# Temp_controlled_fan_2.net
KiCad netlist of a schematic drawn in EAGLE
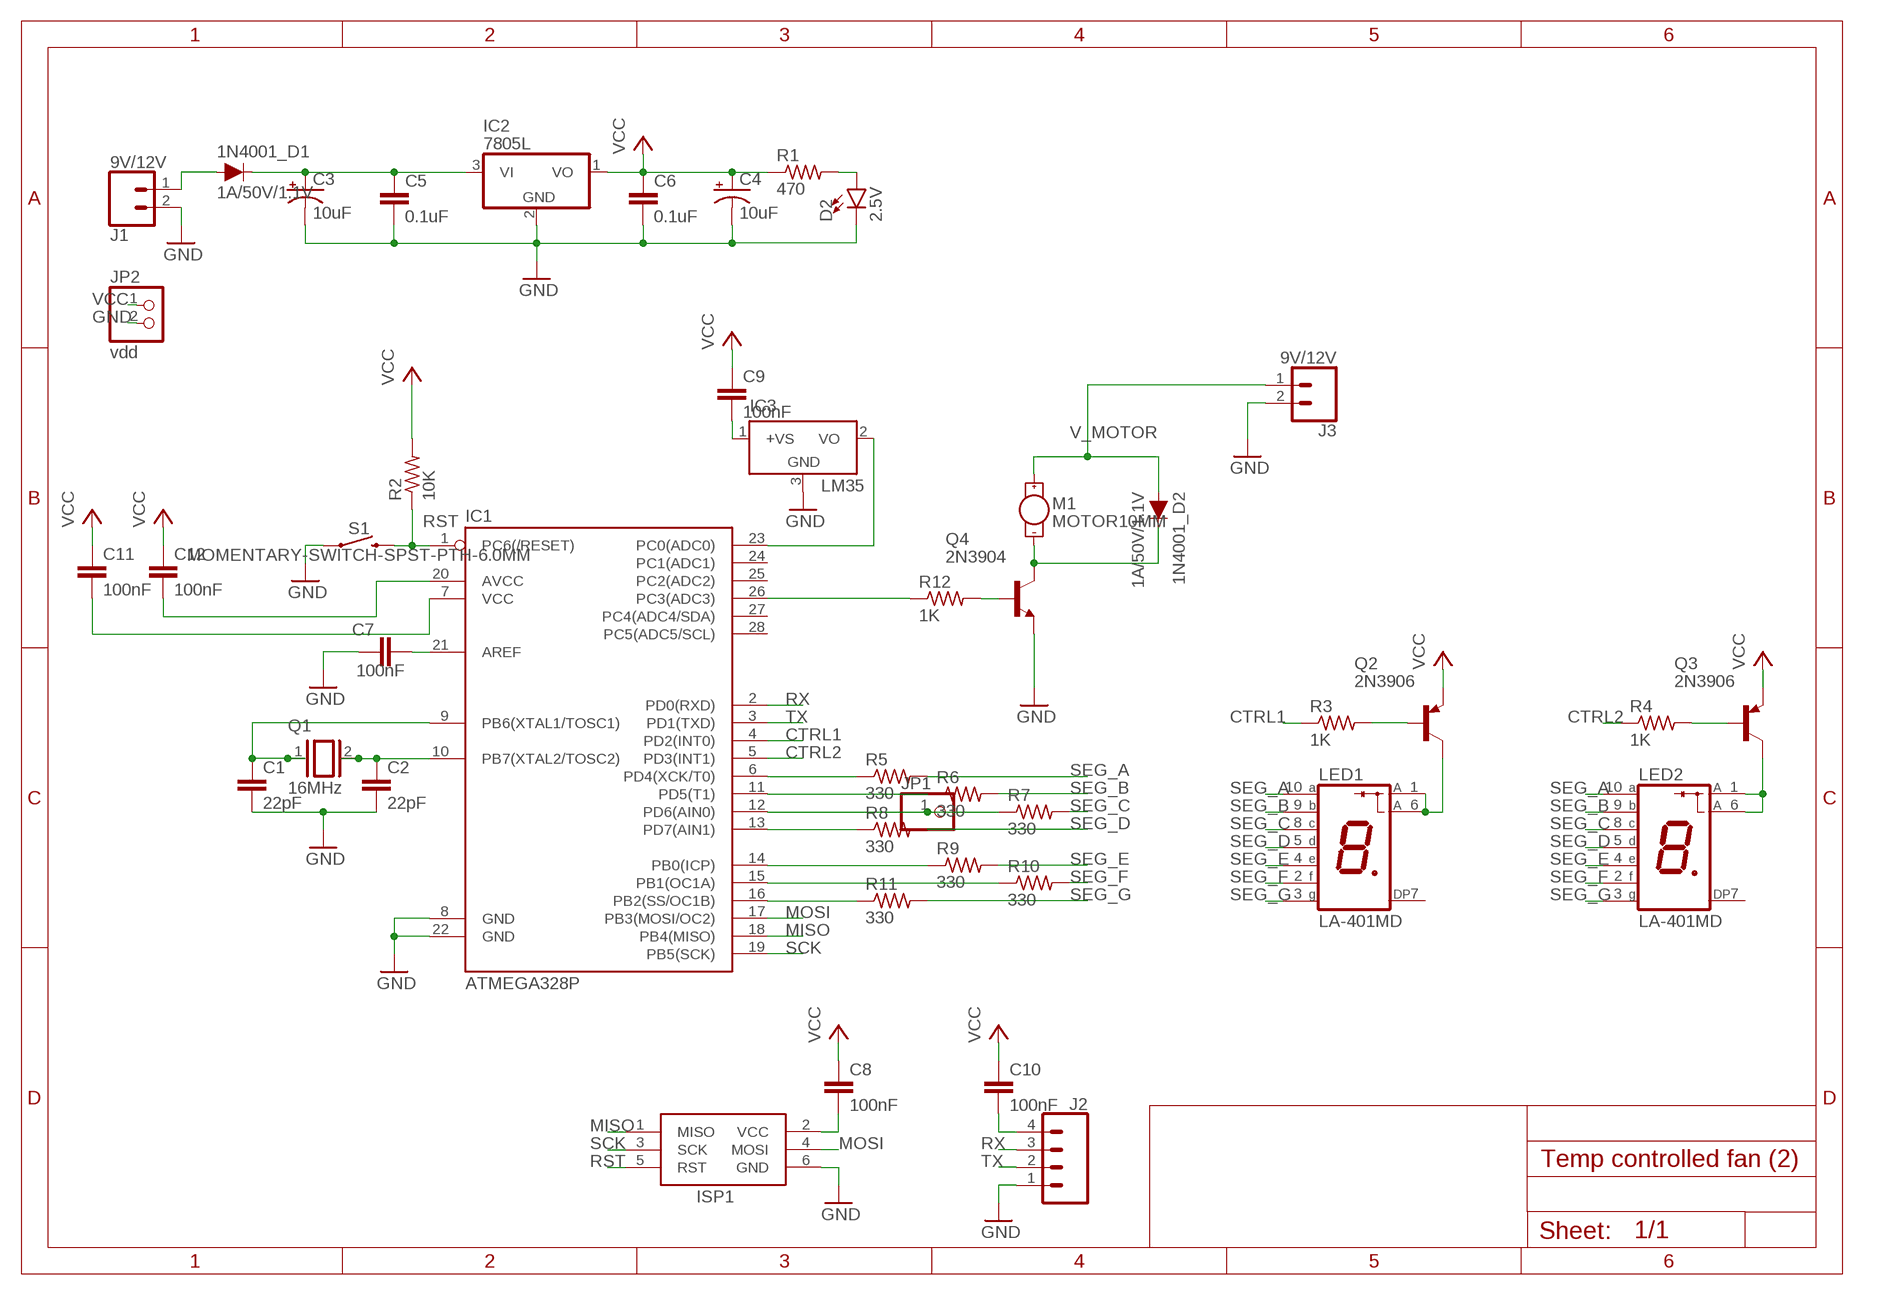
[diagram p0: schematic, sheet 1]

(export (version "E")
  (design (tool "Eeschema 10.0.6"))
  (components
    (comp (ref "1N4001_D1")
      (value "1A/50V/1.1V")
      (footprint "eagle-import:DIODE-1N4001")
      (libsource (lib "eagle-import") (part "DIODE-PTH"))
    )
    (comp (ref "1N4001_D2")
      (value "1A/50V/1.1V")
      (footprint "eagle-import:DIODE-1N4001")
      (libsource (lib "eagle-import") (part "DIODE-PTH"))
    )
    (comp (ref "C1")
      (value "22pF")
      (footprint "eagle-import:0603")
      (libsource (lib "eagle-import") (part "22PF-0603-50V-5%"))
    )
    (comp (ref "C2")
      (value "22pF")
      (footprint "eagle-import:0603")
      (libsource (lib "eagle-import") (part "22PF-0603-50V-5%"))
    )
    (comp (ref "C3")
      (value "10uF")
      (footprint "eagle-import:CPOL-RADIAL-2.5MM-5MM")
      (libsource (lib "eagle-import") (part "10UF-POLAR-RADIAL-2.5MM-25V-20%"))
    )
    (comp (ref "C4")
      (value "10uF")
      (footprint "eagle-import:CPOL-RADIAL-2.5MM-5MM")
      (libsource (lib "eagle-import") (part "10UF-POLAR-RADIAL-2.5MM-25V-20%"))
    )
    (comp (ref "C5")
      (value "0.1uF")
      (footprint "eagle-import:0603")
      (libsource (lib "eagle-import") (part "0.1UF-0603-25V-5%"))
    )
    (comp (ref "C6")
      (value "0.1uF")
      (footprint "eagle-import:0603")
      (libsource (lib "eagle-import") (part "0.1UF-0603-25V-5%"))
    )
    (comp (ref "C7")
      (value "100nF")
      (footprint "eagle-import:0603")
      (libsource (lib "eagle-import") (part "22PF-0603-50V-5%"))
    )
    (comp (ref "C8")
      (value "100nF")
      (footprint "eagle-import:0603")
      (libsource (lib "eagle-import") (part "22PF-0603-50V-5%"))
    )
    (comp (ref "C9")
      (value "100nF")
      (footprint "eagle-import:0603")
      (libsource (lib "eagle-import") (part "22PF-0603-50V-5%"))
    )
    (comp (ref "C10")
      (value "100nF")
      (footprint "eagle-import:0603")
      (libsource (lib "eagle-import") (part "22PF-0603-50V-5%"))
    )
    (comp (ref "C11")
      (value "100nF")
      (footprint "eagle-import:0603")
      (libsource (lib "eagle-import") (part "22PF-0603-50V-5%"))
    )
    (comp (ref "C12")
      (value "100nF")
      (footprint "eagle-import:0603")
      (libsource (lib "eagle-import") (part "22PF-0603-50V-5%"))
    )
    (comp (ref "D2")
      (value "2.5V")
      (footprint "eagle-import:LED-1206")
      (libsource (lib "eagle-import") (part "LED1206"))
    )
    (comp (ref "IC1")
      (value "ATMEGA328P")
      (footprint "eagle-import:DIP28")
      (libsource (lib "eagle-import") (part "ATMEGA328P_PDIP"))
    )
    (comp (ref "IC2")
      (value "7805L")
      (footprint "eagle-import:TO92")
      (libsource (lib "eagle-import") (part "78L05"))
    )
    (comp (ref "IC3")
      (value "LM35")
      (footprint "eagle-import:TO92")
      (libsource (lib "eagle-import") (part "LM35CZ"))
    )
    (comp (ref "ISP1")
      (value "AVRISP-6")
      (footprint "eagle-import:AVRISP")
      (libsource (lib "eagle-import") (part "AVRISP-6"))
    )
    (comp (ref "J1")
      (value "9V/12V")
      (footprint "eagle-import:1X02_RA_PTH_FEMALE")
      (libsource (lib "eagle-import") (part "CONN_02PTH_RA_FEMALE"))
    )
    (comp (ref "J2")
      (value "CONN_04")
      (footprint "eagle-import:1X04")
      (libsource (lib "eagle-import") (part "CONN_04"))
    )
    (comp (ref "J3")
      (value "9V/12V")
      (footprint "eagle-import:1X02_RA_PTH_FEMALE")
      (libsource (lib "eagle-import") (part "CONN_02PTH_RA_FEMALE"))
    )
    (comp (ref "JP1")
      (value "PINHD-1X1")
      (footprint "eagle-import:1X01")
      (libsource (lib "eagle-import") (part "PINHD-1X1"))
    )
    (comp (ref "JP2")
      (value "vdd")
      (footprint "eagle-import:1X02")
      (libsource (lib "eagle-import") (part "PINHD-1X2"))
    )
    (comp (ref "LED1")
      (value "LA-401MD")
      (footprint "eagle-import:LA-401")
      (libsource (lib "eagle-import") (part "LA-401DM"))
    )
    (comp (ref "LED2")
      (value "LA-401MD")
      (footprint "eagle-import:LA-401")
      (libsource (lib "eagle-import") (part "LA-401DM"))
    )
    (comp (ref "M1")
      (value "MOTOR10MM")
      (footprint "eagle-import:VIBE-MOTOR-10MM")
      (libsource (lib "eagle-import") (part "MOTOR10MM"))
    )
    (comp (ref "Q1")
      (value "16MHz")
      (footprint "eagle-import:QS")
      (libsource (lib "eagle-import") (part "XTAL/S"))
    )
    (comp (ref "Q2")
      (value "2N3906")
      (footprint "eagle-import:TO92")
      (libsource (lib "eagle-import") (part "2N3906"))
    )
    (comp (ref "Q3")
      (value "2N3906")
      (footprint "eagle-import:TO92")
      (libsource (lib "eagle-import") (part "2N3906"))
    )
    (comp (ref "Q4")
      (value "2N3904")
      (footprint "eagle-import:TO92")
      (libsource (lib "eagle-import") (part "2N3904"))
    )
    (comp (ref "R1")
      (value "470")
      (footprint "eagle-import:R0805")
      (libsource (lib "eagle-import") (part "R-US_R0805"))
    )
    (comp (ref "R2")
      (value "10K")
      (footprint "eagle-import:R0805")
      (libsource (lib "eagle-import") (part "R-US_R0805"))
    )
    (comp (ref "R3")
      (value "1K")
      (footprint "eagle-import:R0805")
      (libsource (lib "eagle-import") (part "R-US_R0805"))
    )
    (comp (ref "R4")
      (value "1K")
      (footprint "eagle-import:R0805")
      (libsource (lib "eagle-import") (part "R-US_R0805"))
    )
    (comp (ref "R5")
      (value "330")
      (footprint "eagle-import:R0805")
      (libsource (lib "eagle-import") (part "R-US_R0805"))
    )
    (comp (ref "R6")
      (value "330")
      (footprint "eagle-import:R0805")
      (libsource (lib "eagle-import") (part "R-US_R0805"))
    )
    (comp (ref "R7")
      (value "330")
      (footprint "eagle-import:R0805")
      (libsource (lib "eagle-import") (part "R-US_R0805"))
    )
    (comp (ref "R8")
      (value "330")
      (footprint "eagle-import:R0805")
      (libsource (lib "eagle-import") (part "R-US_R0805"))
    )
    (comp (ref "R9")
      (value "330")
      (footprint "eagle-import:R0805")
      (libsource (lib "eagle-import") (part "R-US_R0805"))
    )
    (comp (ref "R10")
      (value "330")
      (footprint "eagle-import:R0805")
      (libsource (lib "eagle-import") (part "R-US_R0805"))
    )
    (comp (ref "R11")
      (value "330")
      (footprint "eagle-import:R0805")
      (libsource (lib "eagle-import") (part "R-US_R0805"))
    )
    (comp (ref "R12")
      (value "1K")
      (footprint "eagle-import:R0805")
      (libsource (lib "eagle-import") (part "R-US_R0805"))
    )
    (comp (ref "S1")
      (value "MOMENTARY-SWITCH-SPST-PTH-6.0MM")
      (footprint "eagle-import:TACTILE_SWITCH_PTH_6.0MM")
      (libsource (lib "eagle-import") (part "MOMENTARY-SWITCH-SPST-PTH-6.0MM"))
    )
  )
  (nets
    (net (code "1") (name "/CTRL1") (class "Default")
      (node (ref "IC1") (pin "4") (pinfunction "PD2(INT0)_4") (pintype "bidirectional"))
      (node (ref "R3") (pin "1") (pinfunction "1_1") (pintype "passive"))
    )
    (net (code "2") (name "/CTRL2") (class "Default")
      (node (ref "IC1") (pin "5") (pinfunction "PD3(INT1)_5") (pintype "bidirectional"))
      (node (ref "R4") (pin "1") (pinfunction "1_1") (pintype "passive"))
    )
    (net (code "3") (name "/MISO") (class "Default")
      (node (ref "IC1") (pin "18") (pinfunction "PB4(MISO)_18") (pintype "bidirectional"))
      (node (ref "ISP1") (pin "1") (pinfunction "MISO_1") (pintype "input"))
    )
    (net (code "4") (name "/MOSI") (class "Default")
      (node (ref "IC1") (pin "17") (pinfunction "PB3(MOSI/OC2)_17") (pintype "bidirectional"))
      (node (ref "ISP1") (pin "4") (pinfunction "MOSI_4") (pintype "output"))
    )
    (net (code "5") (name "/RST") (class "Default")
      (node (ref "IC1") (pin "1") (pinfunction "PC6(/RESET)_1") (pintype "bidirectional"))
      (node (ref "ISP1") (pin "5") (pinfunction "RST_5") (pintype "output"))
      (node (ref "R2") (pin "1") (pinfunction "1_1") (pintype "passive"))
      (node (ref "S1") (pin "3") (pinfunction "2_3") (pintype "passive"))
    )
    (net (code "6") (name "/RX") (class "Default")
      (node (ref "IC1") (pin "2") (pinfunction "PD0(RXD)_2") (pintype "bidirectional"))
      (node (ref "J2") (pin "3") (pinfunction "3_3") (pintype "passive"))
    )
    (net (code "7") (name "/SCK") (class "Default")
      (node (ref "IC1") (pin "19") (pinfunction "PB5(SCK)_19") (pintype "bidirectional"))
      (node (ref "ISP1") (pin "3") (pinfunction "SCK_3") (pintype "output"))
    )
    (net (code "8") (name "/SEG_A") (class "Default")
      (node (ref "LED1") (pin "10") (pinfunction "A_10") (pintype "passive"))
      (node (ref "LED2") (pin "10") (pinfunction "A_10") (pintype "passive"))
      (node (ref "R5") (pin "2") (pinfunction "2_2") (pintype "passive"))
    )
    (net (code "9") (name "/SEG_B") (class "Default")
      (node (ref "LED1") (pin "9") (pinfunction "B_9") (pintype "passive"))
      (node (ref "LED2") (pin "9") (pinfunction "B_9") (pintype "passive"))
      (node (ref "R6") (pin "2") (pinfunction "2_2") (pintype "passive"))
    )
    (net (code "10") (name "/SEG_C") (class "Default")
      (node (ref "LED1") (pin "8") (pinfunction "C_8") (pintype "passive"))
      (node (ref "LED2") (pin "8") (pinfunction "C_8") (pintype "passive"))
      (node (ref "R7") (pin "2") (pinfunction "2_2") (pintype "passive"))
    )
    (net (code "11") (name "/SEG_D") (class "Default")
      (node (ref "LED1") (pin "5") (pinfunction "D_5") (pintype "passive"))
      (node (ref "LED2") (pin "5") (pinfunction "D_5") (pintype "passive"))
      (node (ref "R8") (pin "2") (pinfunction "2_2") (pintype "passive"))
    )
    (net (code "12") (name "/SEG_E") (class "Default")
      (node (ref "LED1") (pin "4") (pinfunction "E_4") (pintype "passive"))
      (node (ref "LED2") (pin "4") (pinfunction "E_4") (pintype "passive"))
      (node (ref "R9") (pin "2") (pinfunction "2_2") (pintype "passive"))
    )
    (net (code "13") (name "/SEG_F") (class "Default")
      (node (ref "LED1") (pin "2") (pinfunction "F_2") (pintype "passive"))
      (node (ref "LED2") (pin "2") (pinfunction "F_2") (pintype "passive"))
      (node (ref "R10") (pin "2") (pinfunction "2_2") (pintype "passive"))
    )
    (net (code "14") (name "/SEG_G") (class "Default")
      (node (ref "LED1") (pin "3") (pinfunction "G_3") (pintype "passive"))
      (node (ref "LED2") (pin "3") (pinfunction "G_3") (pintype "passive"))
      (node (ref "R11") (pin "2") (pinfunction "2_2") (pintype "passive"))
    )
    (net (code "15") (name "/TX") (class "Default")
      (node (ref "IC1") (pin "3") (pinfunction "PD1(TXD)_3") (pintype "bidirectional"))
      (node (ref "J2") (pin "2") (pinfunction "2_2") (pintype "passive"))
    )
    (net (code "16") (name "/V_MOTOR") (class "Default")
      (node (ref "1N4001_D2") (pin "A") (pinfunction "A_A") (pintype "passive"))
      (node (ref "J3") (pin "1") (pinfunction "1_1") (pintype "passive"))
      (node (ref "M1") (pin "+") (pinfunction "+_+") (pintype "bidirectional"))
    )
    (net (code "17") (name "GND") (class "Default")
      (node (ref "C1") (pin "2") (pinfunction "2_2") (pintype "passive"))
      (node (ref "C2") (pin "2") (pinfunction "2_2") (pintype "passive"))
      (node (ref "C3") (pin "2") (pinfunction "-_2") (pintype "passive"))
      (node (ref "C4") (pin "2") (pinfunction "-_2") (pintype "passive"))
      (node (ref "C5") (pin "2") (pinfunction "2_2") (pintype "passive"))
      (node (ref "C6") (pin "2") (pinfunction "2_2") (pintype "passive"))
      (node (ref "C7") (pin "1") (pinfunction "1_1") (pintype "passive"))
      (node (ref "D2") (pin "C") (pinfunction "C_C") (pintype "passive"))
      (node (ref "IC1") (pin "22") (pinfunction "GND_22") (pintype "bidirectional"))
      (node (ref "IC1") (pin "8") (pinfunction "GND_8") (pintype "bidirectional"))
      (node (ref "IC2") (pin "2") (pinfunction "GND_2") (pintype "passive"))
      (node (ref "IC3") (pin "3") (pinfunction "GND_3") (pintype "power_in"))
      (node (ref "ISP1") (pin "6") (pinfunction "GND_6") (pintype "power_in"))
      (node (ref "J1") (pin "2") (pinfunction "2_2") (pintype "passive"))
      (node (ref "J2") (pin "1") (pinfunction "1_1") (pintype "passive"))
      (node (ref "J3") (pin "2") (pinfunction "2_2") (pintype "passive"))
      (node (ref "JP2") (pin "2") (pinfunction "2_2") (pintype "passive"))
      (node (ref "Q4") (pin "3") (pinfunction "E_3") (pintype "passive"))
      (node (ref "S1") (pin "1") (pinfunction "1_1") (pintype "passive"))
    )
    (net (code "18") (name "Net-(1N4001_D1-PadA)") (class "Default")
      (node (ref "1N4001_D1") (pin "A") (pinfunction "A_A") (pintype "passive"))
      (node (ref "J1") (pin "1") (pinfunction "1_1") (pintype "passive"))
    )
    (net (code "19") (name "Net-(C3-+)") (class "Default")
      (node (ref "1N4001_D1") (pin "C") (pinfunction "C_C") (pintype "passive"))
      (node (ref "C3") (pin "1") (pinfunction "+_1") (pintype "passive"))
      (node (ref "C5") (pin "1") (pinfunction "1_1") (pintype "passive"))
      (node (ref "IC2") (pin "3") (pinfunction "VI_3") (pintype "input"))
    )
    (net (code "20") (name "Net-(C10-Pad2)") (class "Default")
      (node (ref "C10") (pin "2") (pinfunction "2_2") (pintype "passive"))
      (node (ref "J2") (pin "4") (pinfunction "4_4") (pintype "passive"))
    )
    (net (code "21") (name "Net-(D2-PadA)") (class "Default")
      (node (ref "D2") (pin "A") (pinfunction "A_A") (pintype "passive"))
      (node (ref "R1") (pin "2") (pinfunction "2_2") (pintype "passive"))
    )
    (net (code "22") (name "Net-(IC1-AREF)") (class "Default")
      (node (ref "C7") (pin "2") (pinfunction "2_2") (pintype "passive"))
      (node (ref "IC1") (pin "21") (pinfunction "AREF_21") (pintype "bidirectional"))
    )
    (net (code "23") (name "Net-(IC1-AVCC)") (class "Default")
      (node (ref "C12") (pin "2") (pinfunction "2_2") (pintype "passive"))
      (node (ref "IC1") (pin "20") (pinfunction "AVCC_20") (pintype "bidirectional"))
    )
    (net (code "24") (name "Net-(IC1-PB0(ICP))") (class "Default")
      (node (ref "IC1") (pin "14") (pinfunction "PB0(ICP)_14") (pintype "bidirectional"))
      (node (ref "R9") (pin "1") (pinfunction "1_1") (pintype "passive"))
    )
    (net (code "25") (name "Net-(IC1-PB1(OC1A))") (class "Default")
      (node (ref "IC1") (pin "15") (pinfunction "PB1(OC1A)_15") (pintype "bidirectional"))
      (node (ref "R10") (pin "1") (pinfunction "1_1") (pintype "passive"))
    )
    (net (code "26") (name "Net-(IC1-PB2(SS{slash}OC1B))") (class "Default")
      (node (ref "IC1") (pin "16") (pinfunction "PB2(SS/OC1B)_16") (pintype "bidirectional"))
      (node (ref "R11") (pin "1") (pinfunction "1_1") (pintype "passive"))
    )
    (net (code "27") (name "Net-(IC1-PB6(XTAL1{slash}TOSC1))") (class "Default")
      (node (ref "C1") (pin "1") (pinfunction "1_1") (pintype "passive"))
      (node (ref "IC1") (pin "9") (pinfunction "PB6(XTAL1/TOSC1)_9") (pintype "bidirectional"))
      (node (ref "Q1") (pin "1") (pinfunction "1_1") (pintype "passive"))
    )
    (net (code "28") (name "Net-(IC1-PB7(XTAL2{slash}TOSC2))") (class "Default")
      (node (ref "C2") (pin "1") (pinfunction "1_1") (pintype "passive"))
      (node (ref "IC1") (pin "10") (pinfunction "PB7(XTAL2/TOSC2)_10") (pintype "bidirectional"))
      (node (ref "Q1") (pin "2") (pinfunction "2_2") (pintype "passive"))
    )
    (net (code "29") (name "Net-(IC1-PC0(ADC0))") (class "Default")
      (node (ref "IC1") (pin "23") (pinfunction "PC0(ADC0)_23") (pintype "bidirectional"))
      (node (ref "IC3") (pin "2") (pinfunction "VO_2") (pintype "input"))
    )
    (net (code "30") (name "Net-(IC1-PC3(ADC3))") (class "Default")
      (node (ref "IC1") (pin "26") (pinfunction "PC3(ADC3)_26") (pintype "bidirectional"))
      (node (ref "R12") (pin "1") (pinfunction "1_1") (pintype "passive"))
    )
    (net (code "31") (name "Net-(IC1-PD4(XCK{slash}T0))") (class "Default")
      (node (ref "IC1") (pin "6") (pinfunction "PD4(XCK/T0)_6") (pintype "bidirectional"))
      (node (ref "R5") (pin "1") (pinfunction "1_1") (pintype "passive"))
    )
    (net (code "32") (name "Net-(IC1-PD5(T1))") (class "Default")
      (node (ref "IC1") (pin "11") (pinfunction "PD5(T1)_11") (pintype "bidirectional"))
      (node (ref "R6") (pin "1") (pinfunction "1_1") (pintype "passive"))
    )
    (net (code "33") (name "Net-(IC1-PD6(AIN0))") (class "Default")
      (node (ref "IC1") (pin "12") (pinfunction "PD6(AIN0)_12") (pintype "bidirectional"))
      (node (ref "JP1") (pin "1") (pinfunction "1_1") (pintype "passive"))
      (node (ref "R7") (pin "1") (pinfunction "1_1") (pintype "passive"))
    )
    (net (code "34") (name "Net-(IC1-PD7(AIN1))") (class "Default")
      (node (ref "IC1") (pin "13") (pinfunction "PD7(AIN1)_13") (pintype "bidirectional"))
      (node (ref "R8") (pin "1") (pinfunction "1_1") (pintype "passive"))
    )
    (net (code "35") (name "Net-(IC1-VCC)") (class "Default")
      (node (ref "C11") (pin "2") (pinfunction "2_2") (pintype "passive"))
      (node (ref "IC1") (pin "7") (pinfunction "VCC_7") (pintype "bidirectional"))
    )
    (net (code "36") (name "Net-(IC3-+VS)") (class "Default")
      (node (ref "C9") (pin "2") (pinfunction "2_2") (pintype "passive"))
      (node (ref "IC3") (pin "1") (pinfunction "+VS_1") (pintype "input"))
    )
    (net (code "37") (name "Net-(ISP1-VCC)") (class "Default")
      (node (ref "C8") (pin "2") (pinfunction "2_2") (pintype "passive"))
      (node (ref "ISP1") (pin "2") (pinfunction "VCC_2") (pintype "power_in"))
    )
    (net (code "38") (name "Net-(Q2-B)") (class "Default")
      (node (ref "Q2") (pin "2") (pinfunction "B_2") (pintype "passive"))
      (node (ref "R3") (pin "2") (pinfunction "2_2") (pintype "passive"))
    )
    (net (code "39") (name "Net-(Q2-C)") (class "Default")
      (node (ref "LED1") (pin "1") (pinfunction "A_1") (pintype "passive"))
      (node (ref "LED1") (pin "6") (pinfunction "A_6") (pintype "passive"))
      (node (ref "Q2") (pin "1") (pinfunction "C_1") (pintype "passive"))
    )
    (net (code "40") (name "Net-(Q3-B)") (class "Default")
      (node (ref "Q3") (pin "2") (pinfunction "B_2") (pintype "passive"))
      (node (ref "R4") (pin "2") (pinfunction "2_2") (pintype "passive"))
    )
    (net (code "41") (name "Net-(Q3-C)") (class "Default")
      (node (ref "LED2") (pin "1") (pinfunction "A_1") (pintype "passive"))
      (node (ref "LED2") (pin "6") (pinfunction "A_6") (pintype "passive"))
      (node (ref "Q3") (pin "1") (pinfunction "C_1") (pintype "passive"))
    )
    (net (code "42") (name "Net-(Q4-B)") (class "Default")
      (node (ref "Q4") (pin "2") (pinfunction "B_2") (pintype "passive"))
      (node (ref "R12") (pin "2") (pinfunction "2_2") (pintype "passive"))
    )
    (net (code "43") (name "Net-(Q4-C)") (class "Default")
      (node (ref "1N4001_D2") (pin "C") (pinfunction "C_C") (pintype "passive"))
      (node (ref "M1") (pin "-") (pinfunction "-_-") (pintype "bidirectional"))
      (node (ref "Q4") (pin "1") (pinfunction "C_1") (pintype "passive"))
    )
    (net (code "44") (name "VCC") (class "Default")
      (node (ref "C10") (pin "1") (pinfunction "1_1") (pintype "passive"))
      (node (ref "C11") (pin "1") (pinfunction "1_1") (pintype "passive"))
      (node (ref "C12") (pin "1") (pinfunction "1_1") (pintype "passive"))
      (node (ref "C4") (pin "1") (pinfunction "+_1") (pintype "passive"))
      (node (ref "C6") (pin "1") (pinfunction "1_1") (pintype "passive"))
      (node (ref "C8") (pin "1") (pinfunction "1_1") (pintype "passive"))
      (node (ref "C9") (pin "1") (pinfunction "1_1") (pintype "passive"))
      (node (ref "IC2") (pin "1") (pinfunction "VO_1") (pintype "passive"))
      (node (ref "JP2") (pin "1") (pinfunction "1_1") (pintype "passive"))
      (node (ref "Q2") (pin "3") (pinfunction "E_3") (pintype "passive"))
      (node (ref "Q3") (pin "3") (pinfunction "E_3") (pintype "passive"))
      (node (ref "R1") (pin "1") (pinfunction "1_1") (pintype "passive"))
      (node (ref "R2") (pin "2") (pinfunction "2_2") (pintype "passive"))
    )
    (net (code "45") (name "unconnected-(IC1-PC1(ADC1)-Pad24)") (class "Default")
      (node (ref "IC1") (pin "24") (pinfunction "PC1(ADC1)_24") (pintype "bidirectional"))
    )
    (net (code "46") (name "unconnected-(IC1-PC2(ADC2)-Pad25)") (class "Default")
      (node (ref "IC1") (pin "25") (pinfunction "PC2(ADC2)_25") (pintype "bidirectional"))
    )
    (net (code "47") (name "unconnected-(IC1-PC4(ADC4{slash}SDA)-Pad27)") (class "Default")
      (node (ref "IC1") (pin "27") (pinfunction "PC4(ADC4/SDA)_27") (pintype "bidirectional"))
    )
    (net (code "48") (name "unconnected-(IC1-PC5(ADC5{slash}SCL)-Pad28)") (class "Default")
      (node (ref "IC1") (pin "28") (pinfunction "PC5(ADC5/SCL)_28") (pintype "bidirectional"))
    )
    (net (code "49") (name "unconnected-(LED1-DP-Pad7)") (class "Default")
      (node (ref "LED1") (pin "7") (pinfunction "DP_7") (pintype "passive"))
    )
    (net (code "50") (name "unconnected-(LED2-DP-Pad7)") (class "Default")
      (node (ref "LED2") (pin "7") (pinfunction "DP_7") (pintype "passive"))
    )
  )
)
